# QUTMS-BrakeLight-S02.net
KiCad netlist of a schematic drawn in Altium Designer
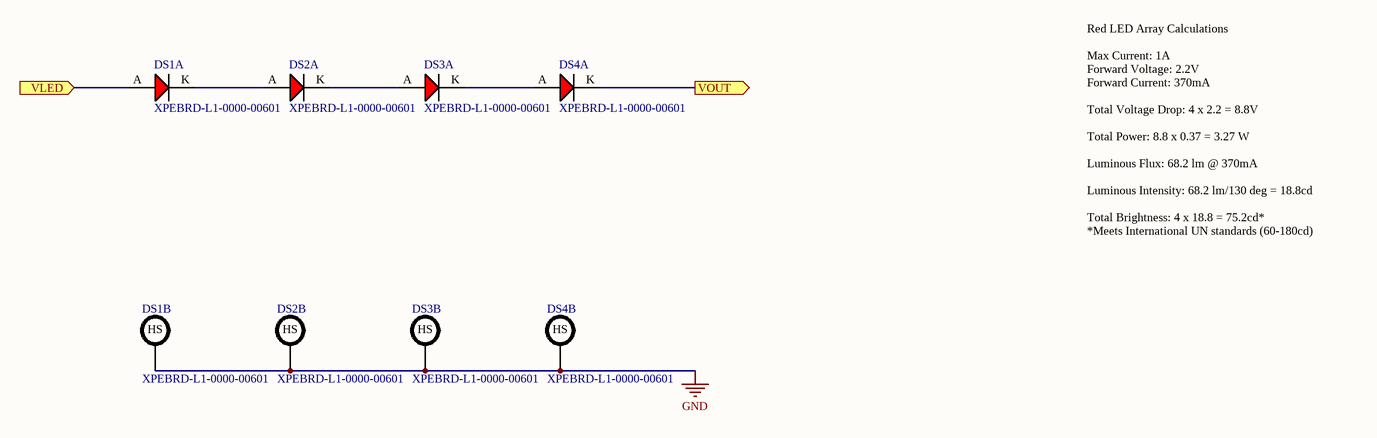
[diagram p0: QUTMS-BrakeLight-S02.SchDoc]

(export (version "E")
  (design (tool "Eeschema 10.0.6"))
  (components
    (comp (ref "DS1")
      (value "XPEBRD-L1-0000-00601")
      (footprint "Cree XLamp XP-E2")
      (description "LED, Cree XLamp XP-E2 Series, Red, 630 nm, 130 °, 62 lm, 1 A")
      (libsource (lib "QUTMS_LEDLibrary") (part "XPEBRD-L1-0000-00601"))
    )
    (comp (ref "DS2")
      (value "XPEBRD-L1-0000-00601")
      (footprint "Cree XLamp XP-E2")
      (description "LED, Cree XLamp XP-E2 Series, Red, 630 nm, 130 °, 62 lm, 1 A")
      (libsource (lib "QUTMS_LEDLibrary") (part "XPEBRD-L1-0000-00601"))
    )
    (comp (ref "DS3")
      (value "XPEBRD-L1-0000-00601")
      (footprint "Cree XLamp XP-E2")
      (description "LED, Cree XLamp XP-E2 Series, Red, 630 nm, 130 °, 62 lm, 1 A")
      (libsource (lib "QUTMS_LEDLibrary") (part "XPEBRD-L1-0000-00601"))
    )
    (comp (ref "DS4")
      (value "XPEBRD-L1-0000-00601")
      (footprint "Cree XLamp XP-E2")
      (description "LED, Cree XLamp XP-E2 Series, Red, 630 nm, 130 °, 62 lm, 1 A")
      (libsource (lib "QUTMS_LEDLibrary") (part "XPEBRD-L1-0000-00601"))
    )
  )
  (nets
    (net (code "1") (name "/VLED") (class "Default")
      (node (ref "DS1") (pin "A") (pinfunction "A_A") (pintype "passive"))
    )
    (net (code "2") (name "/VOUT") (class "Default")
      (node (ref "DS4") (pin "K") (pinfunction "K_K") (pintype "passive"))
    )
    (net (code "3") (name "GND") (class "Default")
      (node (ref "DS1") (pin "HS") (pinfunction "HS_HS") (pintype "passive"))
      (node (ref "DS2") (pin "HS") (pinfunction "HS_HS") (pintype "passive"))
      (node (ref "DS3") (pin "HS") (pinfunction "HS_HS") (pintype "passive"))
      (node (ref "DS4") (pin "HS") (pinfunction "HS_HS") (pintype "passive"))
    )
    (net (code "4") (name "Net-(DS1-PadK)") (class "Default")
      (node (ref "DS1") (pin "K") (pinfunction "K_K") (pintype "passive"))
      (node (ref "DS2") (pin "A") (pinfunction "A_A") (pintype "passive"))
    )
    (net (code "5") (name "Net-(DS2-PadK)") (class "Default")
      (node (ref "DS2") (pin "K") (pinfunction "K_K") (pintype "passive"))
      (node (ref "DS3") (pin "A") (pinfunction "A_A") (pintype "passive"))
    )
    (net (code "6") (name "Net-(DS3-PadK)") (class "Default")
      (node (ref "DS3") (pin "K") (pinfunction "K_K") (pintype "passive"))
      (node (ref "DS4") (pin "A") (pinfunction "A_A") (pintype "passive"))
    )
  )
)
